# STM32_Smart.net
KiCad netlist of a schematic drawn in Altium Designer
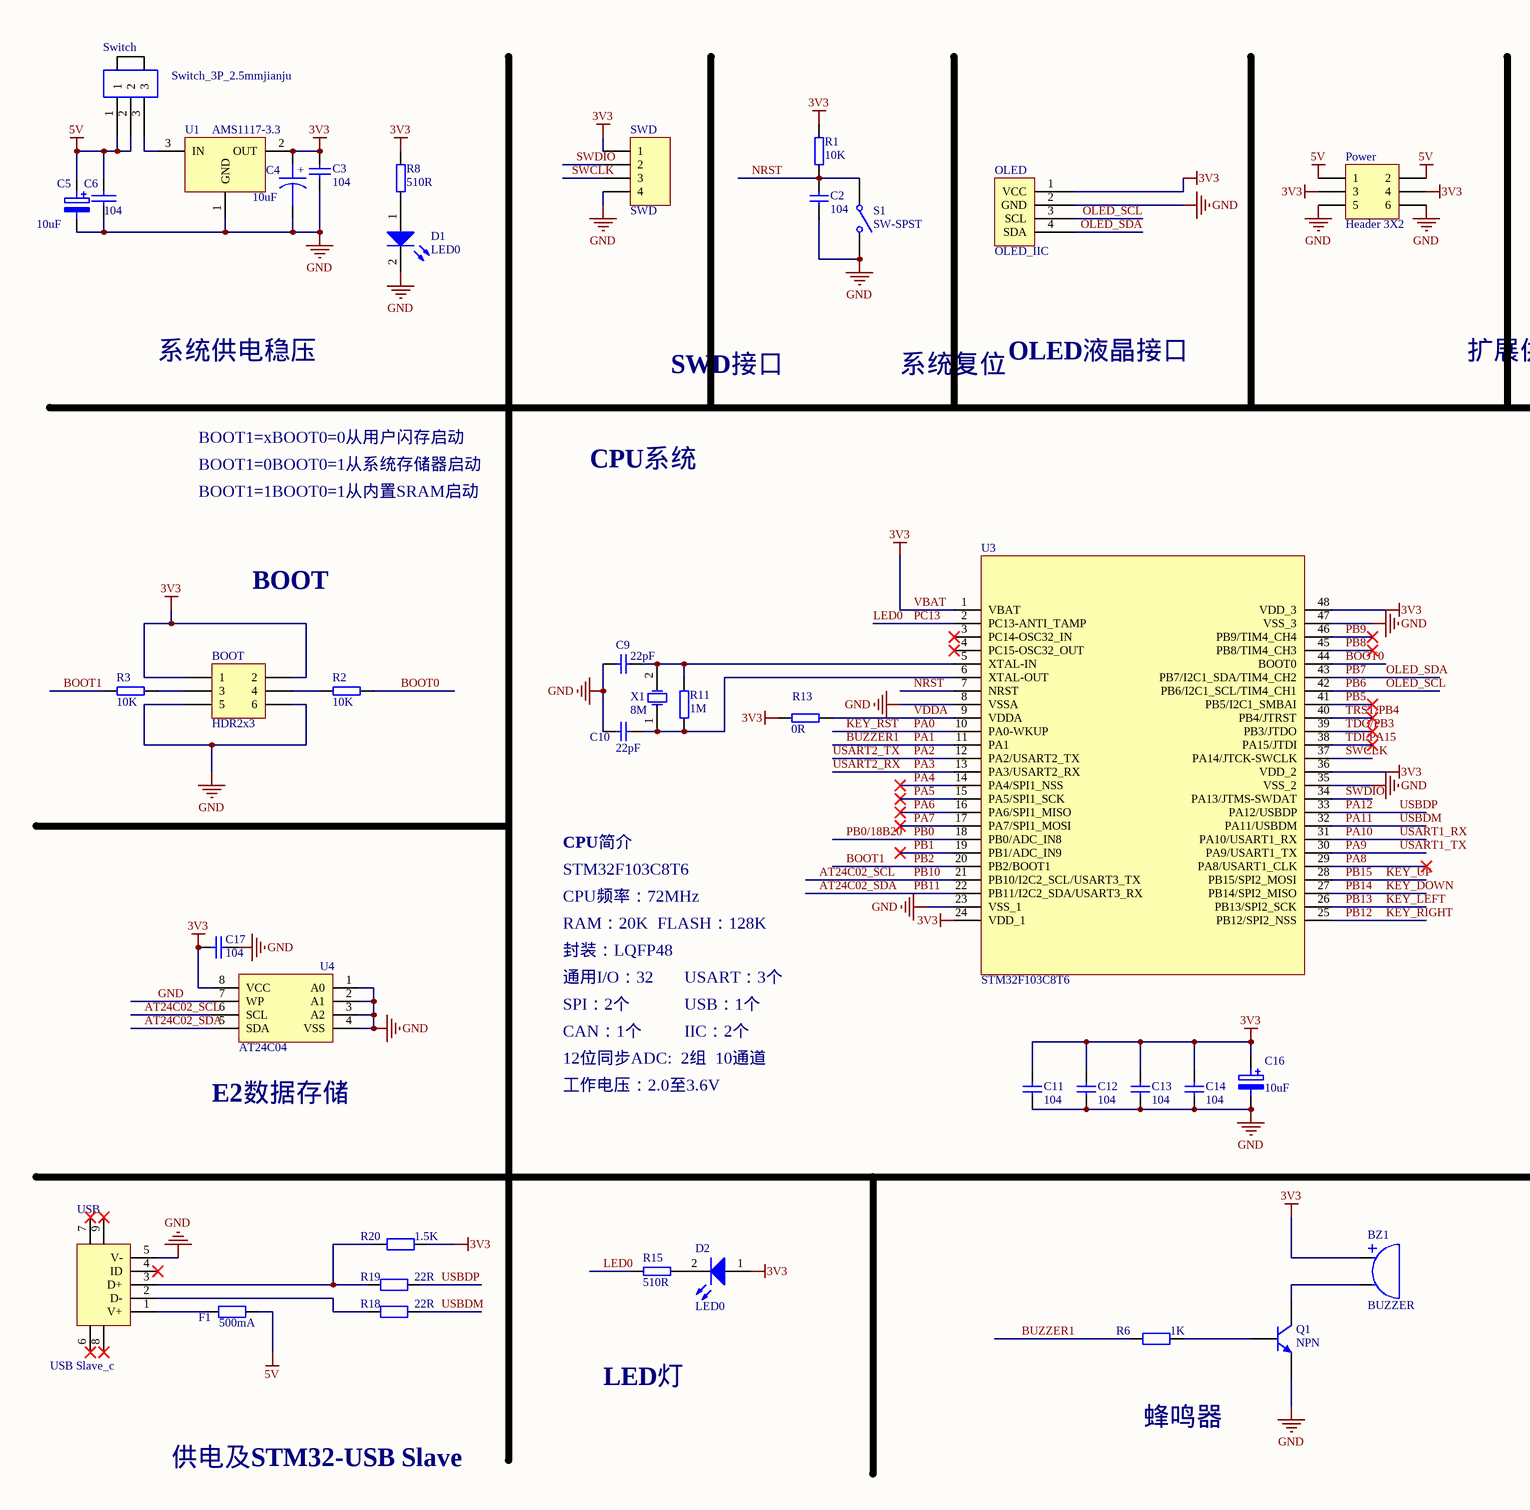
[diagram p0: STM32_Smart.SchDoc, left]
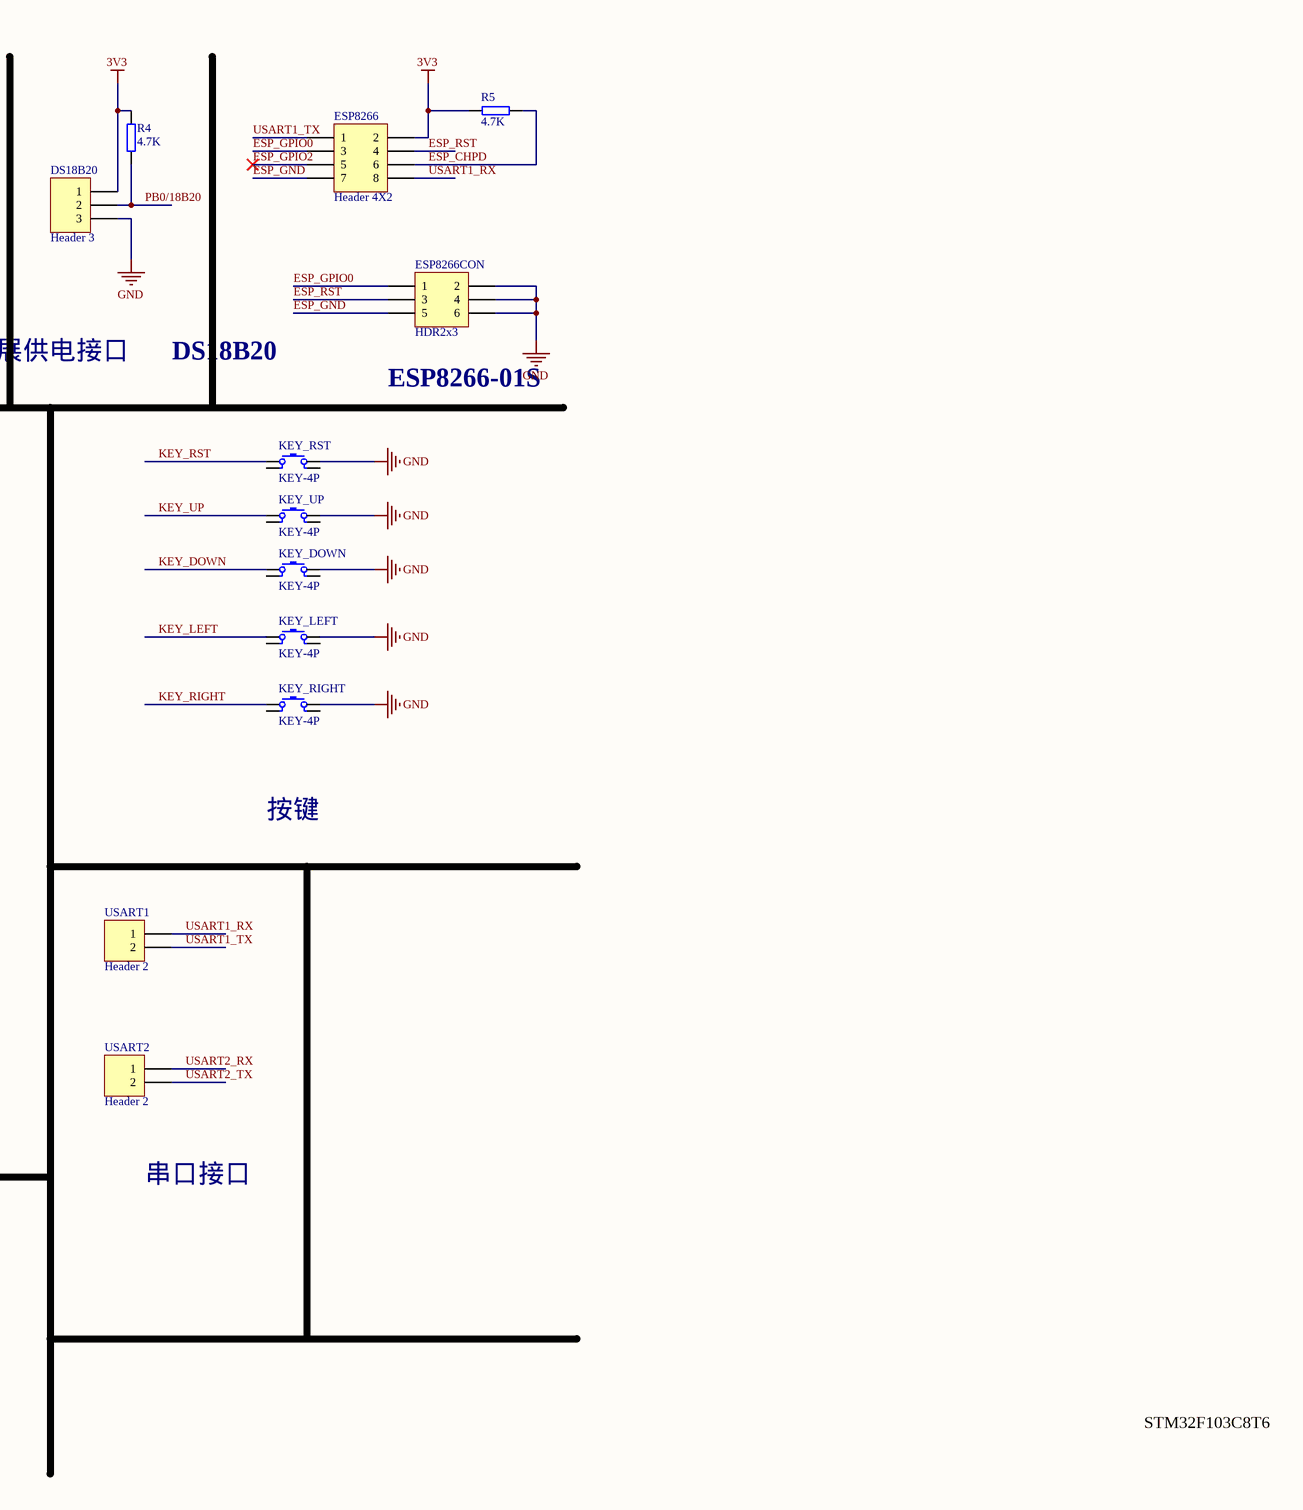
[diagram p1: STM32_Smart.SchDoc, right]

(export (version "E")
  (design (tool "Eeschema 10.0.6"))
  (components
    (comp (ref "BOOT")
      (value "HDR2x3")
      (footprint "PIN-2x3-2.54-1.0")
      (description "Connector")
      (libsource (lib "General") (part "HDR2x3"))
    )
    (comp (ref "BZ1")
      (value "BUZZER")
      (footprint "BUZZER_12*9.5_pin_7.6mm")
      (description "Buzzer")
      (libsource (lib "General") (part "BUZZER"))
    )
    (comp (ref "C2")
      (value "104")
      (footprint "RC0603")
      (description "Capacitor")
      (fields (field (name "PUBLISHER") "ZL_A0OFFICE"))
      (libsource (lib "CommomDevices") (part "CAP1"))
    )
    (comp (ref "C3")
      (value "104")
      (footprint "RC0603")
      (description "Capacitor")
      (fields (field (name "PUBLISHER") "Altium Limited"))
      (libsource (lib "*") (part "Cap"))
    )
    (comp (ref "C4")
      (value "10uF")
      (footprint "RC0805")
      (description "Capacitor")
      (libsource (lib "*") (part "CAPACITOR POL"))
    )
    (comp (ref "C5") (value "10uF") (footprint "RC0805") (libsource (lib "*") (part "ELECTRO2")))
    (comp (ref "C6")
      (value "104")
      (footprint "RC0603")
      (description "Capacitor")
      (libsource (lib "*") (part "CAP"))
    )
    (comp (ref "C9")
      (value "22pF")
      (footprint "RC0603")
      (description "Capacitor")
      (fields (field (name "PUBLISHER") "ZL_A0OFFICE"))
      (libsource (lib "CommomDevices") (part "CAP1"))
    )
    (comp (ref "C10")
      (value "22pF")
      (footprint "RC0603")
      (description "Capacitor")
      (fields (field (name "PUBLISHER") "ZL_A0OFFICE"))
      (libsource (lib "CommomDevices") (part "CAP1"))
    )
    (comp (ref "C11")
      (value "104")
      (footprint "RC0603")
      (description "Capacitor")
      (fields (field (name "PUBLISHER") "ZL_A0OFFICE"))
      (libsource (lib "CommomDevices") (part "CAP1"))
    )
    (comp (ref "C12")
      (value "104")
      (footprint "RC0603")
      (description "Capacitor")
      (fields (field (name "PUBLISHER") "ZL_A0OFFICE"))
      (libsource (lib "CommomDevices") (part "CAP1"))
    )
    (comp (ref "C13")
      (value "104")
      (footprint "RC0603")
      (description "Capacitor")
      (fields (field (name "PUBLISHER") "ZL_A0OFFICE"))
      (libsource (lib "CommomDevices") (part "CAP1"))
    )
    (comp (ref "C14")
      (value "104")
      (footprint "RC0603")
      (description "Capacitor")
      (fields (field (name "PUBLISHER") "ZL_A0OFFICE"))
      (libsource (lib "CommomDevices") (part "CAP1"))
    )
    (comp (ref "C16") (value "10uF") (footprint "RC0805") (libsource (lib "*") (part "ELECTRO2")))
    (comp (ref "C17")
      (value "104")
      (footprint "RC0603")
      (description "Capacitor")
      (libsource (lib "Miscellaneous Devices") (part "Cap"))
    )
    (comp (ref "D1")
      (value "LED0")
      (footprint "LED0805")
      (description "Typical INFRARED GaAs LED")
      (libsource (lib "Miscellaneous Devices") (part "LED0"))
    )
    (comp (ref "D2")
      (value "LED0")
      (footprint "LED0805")
      (description "Typical INFRARED GaAs LED")
      (libsource (lib "Miscellaneous Devices") (part "LED0"))
    )
    (comp (ref "DS18B20")
      (value "Header 3")
      (footprint "HDR1X3")
      (description "Header, 3-Pin")
      (fields (field (name "PUBLISHER") "Altium Limited"))
      (libsource (lib "Miscellaneous Connectors") (part "Header 3"))
    )
    (comp (ref "ESP8266")
      (value "Header 4X2")
      (footprint "HDR2X4")
      (description "Header, 4-Pin, Dual row")
      (fields (field (name "PUBLISHER") "Altium Limited"))
      (libsource (lib "Miscellaneous Connectors") (part "Header 4X2"))
    )
    (comp (ref "ESP8266CON")
      (value "HDR2x3")
      (footprint "PIN-2x3-2.54-1.0")
      (description "Connector")
      (libsource (lib "General") (part "HDR2x3"))
    )
    (comp (ref "F1")
      (value "500mA")
      (footprint "RC0805")
      (description "Resistor")
      (libsource (lib "") (part "Res2_1"))
    )
    (comp (ref "KEY_DOWN")
      (value "KEY-4P")
      (footprint "KEY_6.5x4.5")
      (description "Key")
      (libsource (lib "General") (part "KEY-4P"))
    )
    (comp (ref "KEY_LEFT")
      (value "KEY-4P")
      (footprint "KEY_6.5x4.5")
      (description "Key")
      (libsource (lib "General") (part "KEY-4P"))
    )
    (comp (ref "KEY_RIGHT")
      (value "KEY-4P")
      (footprint "KEY_6.5x4.5")
      (description "Key")
      (libsource (lib "General") (part "KEY-4P"))
    )
    (comp (ref "KEY_RST")
      (value "KEY-4P")
      (footprint "KEY_6.5x4.5")
      (description "Key")
      (libsource (lib "General") (part "KEY-4P"))
    )
    (comp (ref "KEY_UP")
      (value "KEY-4P")
      (footprint "KEY_6.5x4.5")
      (description "Key")
      (libsource (lib "General") (part "KEY-4P"))
    )
    (comp (ref "OLED")
      (value "OLED_IIC")
      (footprint "OLED_IIC")
      (libsource (lib "altium-import") (part "root_0_OLED_IIC_"))
    )
    (comp (ref "Power")
      (value "Header 3X2")
      (footprint "IDE3X2-2.54")
      (description "Header, 3-Pin, Dual row")
      (fields (field (name "PUBLISHER") "Altium Limited"))
      (libsource (lib "Miscellaneous Connectors") (part "Header 3X2"))
    )
    (comp (ref "Q1")
      (value "NPN")
      (footprint "TO-92")
      (description "NPN Bipolar Transistor")
      (fields (field (name "PUBLISHER") "Altium Limited"))
      (libsource (lib "Miscellaneous Devices") (part "NPN"))
    )
    (comp (ref "R1") (value "10K") (footprint "RC0603") (libsource (lib "ZIBO V2.0_Main") (part "R")))
    (comp (ref "R2") (value "10K") (footprint "RC0603") (libsource (lib "ZIBO V2.0_Main") (part "R")))
    (comp (ref "R3") (value "10K") (footprint "RC0603") (libsource (lib "ZIBO V2.0_Main") (part "R")))
    (comp (ref "R4") (value "4.7K") (footprint "RC0603") (libsource (lib "ZIBO V2.0_Main") (part "R")))
    (comp (ref "R5") (value "4.7K") (footprint "RC0603") (libsource (lib "ZIBO V2.0_Main") (part "R")))
    (comp (ref "R6")
      (value "1K")
      (footprint "RC0603")
      (description "Resistor")
      (libsource (lib "Miscellaneous Devices") (part "Res2"))
    )
    (comp (ref "R8") (value "510R") (footprint "RC0603") (libsource (lib "ZIBO V2.0_Main") (part "R")))
    (comp (ref "R11") (value "1M") (footprint "RC0603") (libsource (lib "ZIBO V2.0_Main") (part "R")))
    (comp (ref "R13") (value "0R") (footprint "RC0603") (libsource (lib "ZIBO V2.0_Main") (part "R")))
    (comp (ref "R15") (value "510R") (footprint "RC0603") (libsource (lib "ZIBO V2.0_Main") (part "R")))
    (comp (ref "R18")
      (value "22R")
      (footprint "RC0603")
      (description "Resistor")
      (libsource (lib "Miscellaneous Devices") (part "Res2"))
    )
    (comp (ref "R19")
      (value "22R")
      (footprint "RC0603")
      (description "Resistor")
      (libsource (lib "Miscellaneous Devices") (part "Res2"))
    )
    (comp (ref "R20")
      (value "1.5K")
      (footprint "RC0603")
      (description "Resistor")
      (libsource (lib "Miscellaneous Devices") (part "Res2"))
    )
    (comp (ref "S1")
      (value "SW-SPST")
      (footprint "SMT-KEY")
      (description "Single-Pole, Single-Throw Switch")
      (libsource (lib "Miscellaneous Devices") (part "SW-SPST"))
    )
    (comp (ref "SWD")
      (value "SWD")
      (footprint "HDR1X4")
      (description "Header, 4-Pin")
      (fields (field (name "PUBLISHER") "Altium Limited"))
      (libsource (lib "Miscellaneous Connectors") (part "Header 4"))
    )
    (comp (ref "Switch")
      (value "Switch_3P_2.5mmjianju")
      (footprint "Switch_3p_2.5mmjianju")
      (libsource (lib "STM32_Smart") (part "Switch_3P_2.5mmjianju"))
    )
    (comp (ref "U1")
      (value "AMS1117-3.3")
      (footprint "SOT223")
      (libsource (lib "Newcapec9263_Board_NEW") (part "LT1085CM-3.3"))
    )
    (comp (ref "U3")
      (value "STM32F103C8T6")
      (footprint "LQFP48")
      (libsource (lib "STM32_Smart") (part "STM32F103C8T6"))
    )
    (comp (ref "U4") (value "AT24C04") (footprint "SOIC-8P") (libsource (lib "Newcapec9263") (part "EPROM")))
    (comp (ref "USART1")
      (value "Header 2")
      (footprint "HDR1X2")
      (description "Header, 2-Pin")
      (fields (field (name "PUBLISHER") "Altium Limited"))
      (libsource (lib "Miscellaneous Connectors") (part "Header 2"))
    )
    (comp (ref "USART2")
      (value "Header 2")
      (footprint "HDR1X2")
      (description "Header, 2-Pin")
      (fields (field (name "PUBLISHER") "Altium Limited"))
      (libsource (lib "Miscellaneous Connectors") (part "Header 2"))
    )
    (comp (ref "USB")
      (value "USB Slave_c")
      (footprint "MICRO USB CONNECTOR TYPEB-ST-MC-5F-01")
      (description "USB Connector")
      (libsource (lib "General") (part "MICRO USB CONNECTOR TYPEB"))
    )
    (comp (ref "X1")
      (value "8M")
      (footprint "SMD49S")
      (description "Crystal Oscillator")
      (fields (field (name "PUBLISHER") "ZL_A0OFFICE"))
      (libsource (lib "CommomDevices") (part "XTAL_SMD"))
    )
  )
  (nets
    (net (code "1") (name "/AT24C02_SCL") (class "Default")
      (node (ref "U3") (pin "21") (pinfunction "PB10/I2C2_SCL/USART3_TX_21") (pintype "passive"))
      (node (ref "U4") (pin "6") (pinfunction "SCL_6") (pintype "passive"))
    )
    (net (code "2") (name "/AT24C02_SDA") (class "Default")
      (node (ref "U3") (pin "22") (pinfunction "PB11/I2C2_SDA/USART3_RX_22") (pintype "passive"))
      (node (ref "U4") (pin "5") (pinfunction "SDA_5") (pintype "passive"))
    )
    (net (code "3") (name "/BOOT0") (class "Default")
      (node (ref "R2") (pin "1") (pinfunction "1_1") (pintype "passive"))
      (node (ref "U3") (pin "44") (pinfunction "BOOT0_44") (pintype "passive"))
    )
    (net (code "4") (name "/BOOT1") (class "Default")
      (node (ref "R3") (pin "2") (pinfunction "2_2") (pintype "passive"))
      (node (ref "U3") (pin "20") (pinfunction "PB2/BOOT1_20") (pintype "passive"))
    )
    (net (code "5") (name "/BUZZER1") (class "Default")
      (node (ref "R6") (pin "2") (pinfunction "2_2") (pintype "passive"))
      (node (ref "U3") (pin "11") (pinfunction "PA1_11") (pintype "passive"))
    )
    (net (code "6") (name "/ESP_CHPD") (class "Default")
      (node (ref "ESP8266") (pin "6") (pinfunction "6_6") (pintype "passive"))
      (node (ref "R5") (pin "2") (pinfunction "2_2") (pintype "passive"))
    )
    (net (code "7") (name "/ESP_GND") (class "Default")
      (node (ref "ESP8266") (pin "7") (pinfunction "7_7") (pintype "passive"))
      (node (ref "ESP8266CON") (pin "5") (pinfunction "5_5") (pintype "passive"))
    )
    (net (code "8") (name "/ESP_GPIO0") (class "Default")
      (node (ref "ESP8266") (pin "3") (pinfunction "3_3") (pintype "passive"))
      (node (ref "ESP8266CON") (pin "1") (pinfunction "1_1") (pintype "passive"))
    )
    (net (code "9") (name "/ESP_GPIO2") (class "Default")
      (node (ref "ESP8266") (pin "5") (pinfunction "5_5") (pintype "passive+no_connect"))
    )
    (net (code "10") (name "/ESP_RST") (class "Default")
      (node (ref "ESP8266") (pin "4") (pinfunction "4_4") (pintype "passive"))
      (node (ref "ESP8266CON") (pin "3") (pinfunction "3_3") (pintype "passive"))
    )
    (net (code "11") (name "/KEY_DOWN") (class "Default")
      (node (ref "KEY_DOWN") (pin "1") (pinfunction "1_1") (pintype "passive"))
      (node (ref "U3") (pin "27") (pinfunction "PB14/SPI2_MISO_27") (pintype "passive"))
    )
    (net (code "12") (name "/KEY_LEFT") (class "Default")
      (node (ref "KEY_LEFT") (pin "1") (pinfunction "1_1") (pintype "passive"))
      (node (ref "U3") (pin "26") (pinfunction "PB13/SPI2_SCK_26") (pintype "passive"))
    )
    (net (code "13") (name "/KEY_RIGHT") (class "Default")
      (node (ref "KEY_RIGHT") (pin "1") (pinfunction "1_1") (pintype "passive"))
      (node (ref "U3") (pin "25") (pinfunction "PB12/SPI2_NSS_25") (pintype "passive"))
    )
    (net (code "14") (name "/KEY_RST") (class "Default")
      (node (ref "KEY_RST") (pin "1") (pinfunction "1_1") (pintype "passive"))
      (node (ref "U3") (pin "10") (pinfunction "PA0-WKUP_10") (pintype "passive"))
    )
    (net (code "15") (name "/KEY_UP") (class "Default")
      (node (ref "KEY_UP") (pin "1") (pinfunction "1_1") (pintype "passive"))
      (node (ref "U3") (pin "28") (pinfunction "PB15/SPI2_MOSI_28") (pintype "passive"))
    )
    (net (code "16") (name "/LED0") (class "Default")
      (node (ref "R15") (pin "1") (pinfunction "1_1") (pintype "passive"))
      (node (ref "U3") (pin "2") (pinfunction "PC13-ANTI_TAMP_2") (pintype "passive"))
    )
    (net (code "17") (name "/NRST") (class "Default")
      (node (ref "C2") (pin "1") (pinfunction "1_1") (pintype "passive"))
      (node (ref "R1") (pin "1") (pinfunction "1_1") (pintype "passive"))
      (node (ref "S1") (pin "1") (pinfunction "COMMON_1") (pintype "passive"))
      (node (ref "U3") (pin "7") (pinfunction "NRST_7") (pintype "passive"))
    )
    (net (code "18") (name "/OLED_SCL") (class "Default")
      (node (ref "OLED") (pin "3") (pinfunction "SCL_3") (pintype "passive"))
      (node (ref "U3") (pin "42") (pinfunction "PB6/I2C1_SCL/TIM4_CH1_42") (pintype "passive"))
    )
    (net (code "19") (name "/OLED_SDA") (class "Default")
      (node (ref "OLED") (pin "4") (pinfunction "SDA_4") (pintype "passive"))
      (node (ref "U3") (pin "43") (pinfunction "PB7/I2C1_SDA/TIM4_CH2_43") (pintype "passive"))
    )
    (net (code "20") (name "/PA2") (class "Default")
      (node (ref "U3") (pin "12") (pinfunction "PA2/USART2_TX_12") (pintype "passive"))
      (node (ref "USART2") (pin "2") (pinfunction "2_2") (pintype "passive"))
    )
    (net (code "21") (name "/PA3") (class "Default")
      (node (ref "U3") (pin "13") (pinfunction "PA3/USART2_RX_13") (pintype "passive"))
      (node (ref "USART2") (pin "1") (pinfunction "1_1") (pintype "passive"))
    )
    (net (code "22") (name "/PA4") (class "Default")
      (node (ref "U3") (pin "14") (pinfunction "PA4/SPI1_NSS_14") (pintype "passive+no_connect"))
    )
    (net (code "23") (name "/PA5") (class "Default")
      (node (ref "U3") (pin "15") (pinfunction "PA5/SPI1_SCK_15") (pintype "passive+no_connect"))
    )
    (net (code "24") (name "/PA6") (class "Default")
      (node (ref "U3") (pin "16") (pinfunction "PA6/SPI1_MISO_16") (pintype "passive+no_connect"))
    )
    (net (code "25") (name "/PA7") (class "Default")
      (node (ref "U3") (pin "17") (pinfunction "PA7/SPI1_MOSI_17") (pintype "passive+no_connect"))
    )
    (net (code "26") (name "/PA8") (class "Default")
      (node (ref "U3") (pin "29") (pinfunction "PA8/USART1_CLK_29") (pintype "passive+no_connect"))
    )
    (net (code "27") (name "/PA9") (class "Default")
      (node (ref "ESP8266") (pin "1") (pinfunction "1_1") (pintype "passive"))
      (node (ref "U3") (pin "30") (pinfunction "PA9/USART1_TX_30") (pintype "passive"))
      (node (ref "USART1") (pin "2") (pinfunction "2_2") (pintype "passive"))
    )
    (net (code "28") (name "/PA10") (class "Default")
      (node (ref "ESP8266") (pin "8") (pinfunction "8_8") (pintype "passive"))
      (node (ref "U3") (pin "31") (pinfunction "PA10/USART1_RX_31") (pintype "passive"))
      (node (ref "USART1") (pin "1") (pinfunction "1_1") (pintype "passive"))
    )
    (net (code "29") (name "/PA11") (class "Default")
      (node (ref "R18") (pin "1") (pinfunction "1_1") (pintype "passive"))
      (node (ref "U3") (pin "32") (pinfunction "PA11/USBDM_32") (pintype "passive"))
    )
    (net (code "30") (name "/PA12") (class "Default")
      (node (ref "R19") (pin "1") (pinfunction "1_1") (pintype "passive"))
      (node (ref "U3") (pin "33") (pinfunction "PA12/USBDP_33") (pintype "passive"))
    )
    (net (code "31") (name "/PB0") (class "Default")
      (node (ref "DS18B20") (pin "2") (pinfunction "2_2") (pintype "passive"))
      (node (ref "R4") (pin "2") (pinfunction "2_2") (pintype "passive"))
      (node (ref "U3") (pin "18") (pinfunction "PB0/ADC_IN8_18") (pintype "passive"))
    )
    (net (code "32") (name "/PB1") (class "Default")
      (node (ref "U3") (pin "19") (pinfunction "PB1/ADC_IN9_19") (pintype "passive+no_connect"))
    )
    (net (code "33") (name "/PB5") (class "Default")
      (node (ref "U3") (pin "41") (pinfunction "PB5/I2C1_SMBAI_41") (pintype "passive+no_connect"))
    )
    (net (code "34") (name "/PB8") (class "Default")
      (node (ref "U3") (pin "45") (pinfunction "PB8/TIM4_CH3_45") (pintype "passive+no_connect"))
    )
    (net (code "35") (name "/PB9") (class "Default")
      (node (ref "U3") (pin "46") (pinfunction "PB9/TIM4_CH4_46") (pintype "passive+no_connect"))
    )
    (net (code "36") (name "/SWCLK") (class "Default")
      (node (ref "SWD") (pin "3") (pinfunction "3_3") (pintype "passive"))
      (node (ref "U3") (pin "37") (pinfunction "PA14/JTCK-SWCLK_37") (pintype "passive"))
    )
    (net (code "37") (name "/SWDIO") (class "Default")
      (node (ref "SWD") (pin "2") (pinfunction "2_2") (pintype "passive"))
      (node (ref "U3") (pin "34") (pinfunction "PA13/JTMS-SWDAT_34") (pintype "passive"))
    )
    (net (code "38") (name "/TDI{slash}PA15") (class "Default")
      (node (ref "U3") (pin "38") (pinfunction "PA15/JTDI_38") (pintype "passive+no_connect"))
    )
    (net (code "39") (name "/TDO{slash}PB3") (class "Default")
      (node (ref "U3") (pin "39") (pinfunction "PB3/JTDO_39") (pintype "passive+no_connect"))
    )
    (net (code "40") (name "/TRST{slash}PB4") (class "Default")
      (node (ref "U3") (pin "40") (pinfunction "PB4/JTRST_40") (pintype "passive+no_connect"))
    )
    (net (code "41") (name "/VDDA") (class "Default")
      (node (ref "R13") (pin "1") (pinfunction "1_1") (pintype "passive"))
      (node (ref "U3") (pin "9") (pinfunction "VDDA_9") (pintype "passive"))
    )
    (net (code "42") (name "3V3") (class "Default")
      (node (ref "BOOT") (pin "1") (pinfunction "1_1") (pintype "passive"))
      (node (ref "BOOT") (pin "2") (pinfunction "2_2") (pintype "passive"))
      (node (ref "BZ1") (pin "1") (pinfunction "1_1") (pintype "passive"))
      (node (ref "C11") (pin "1") (pinfunction "1_1") (pintype "passive"))
      (node (ref "C12") (pin "1") (pinfunction "1_1") (pintype "passive"))
      (node (ref "C13") (pin "1") (pinfunction "1_1") (pintype "passive"))
      (node (ref "C14") (pin "1") (pinfunction "1_1") (pintype "passive"))
      (node (ref "C16") (pin "1") (pintype "passive"))
      (node (ref "C17") (pin "2") (pinfunction "2_2") (pintype "passive"))
      (node (ref "C3") (pin "1") (pinfunction "1_1") (pintype "passive"))
      (node (ref "C4") (pin "1") (pinfunction "1_1") (pintype "passive"))
      (node (ref "D2") (pin "1") (pinfunction "A_1") (pintype "passive"))
      (node (ref "DS18B20") (pin "1") (pinfunction "1_1") (pintype "passive"))
      (node (ref "ESP8266") (pin "2") (pinfunction "2_2") (pintype "passive"))
      (node (ref "OLED") (pin "1") (pinfunction "VCC_1") (pintype "passive"))
      (node (ref "Power") (pin "3") (pinfunction "3_3") (pintype "passive"))
      (node (ref "Power") (pin "4") (pinfunction "4_4") (pintype "passive"))
      (node (ref "R1") (pin "2") (pinfunction "2_2") (pintype "passive"))
      (node (ref "R13") (pin "2") (pinfunction "2_2") (pintype "passive"))
      (node (ref "R20") (pin "1") (pinfunction "1_1") (pintype "passive"))
      (node (ref "R4") (pin "1") (pinfunction "1_1") (pintype "passive"))
      (node (ref "R5") (pin "1") (pinfunction "1_1") (pintype "passive"))
      (node (ref "R8") (pin "2") (pinfunction "2_2") (pintype "passive"))
      (node (ref "SWD") (pin "1") (pinfunction "1_1") (pintype "passive"))
      (node (ref "U1") (pin "2") (pinfunction "OUT_2") (pintype "passive"))
      (node (ref "U3") (pin "1") (pinfunction "VBAT_1") (pintype "passive"))
      (node (ref "U3") (pin "24") (pinfunction "VDD_1_24") (pintype "passive"))
      (node (ref "U3") (pin "36") (pinfunction "VDD_2_36") (pintype "passive"))
      (node (ref "U3") (pin "48") (pinfunction "VDD_3_48") (pintype "passive"))
      (node (ref "U4") (pin "8") (pinfunction "VCC_8") (pintype "passive"))
    )
    (net (code "43") (name "5V") (class "Default")
      (node (ref "C5") (pin "1") (pintype "passive"))
      (node (ref "C6") (pin "1") (pinfunction "1_1") (pintype "passive"))
      (node (ref "F1") (pin "1") (pinfunction "1_1") (pintype "passive"))
      (node (ref "Power") (pin "1") (pinfunction "1_1") (pintype "passive"))
      (node (ref "Power") (pin "2") (pinfunction "2_2") (pintype "passive"))
      (node (ref "Switch") (pin "1") (pinfunction "1_1") (pintype "passive"))
      (node (ref "Switch") (pin "2") (pinfunction "2_2") (pintype "passive"))
    )
    (net (code "44") (name "GND") (class "Default")
      (node (ref "BOOT") (pin "5") (pinfunction "5_5") (pintype "passive"))
      (node (ref "BOOT") (pin "6") (pinfunction "6_6") (pintype "passive"))
      (node (ref "C10") (pin "2") (pinfunction "2_2") (pintype "passive"))
      (node (ref "C11") (pin "2") (pinfunction "2_2") (pintype "passive"))
      (node (ref "C12") (pin "2") (pinfunction "2_2") (pintype "passive"))
      (node (ref "C13") (pin "2") (pinfunction "2_2") (pintype "passive"))
      (node (ref "C14") (pin "2") (pinfunction "2_2") (pintype "passive"))
      (node (ref "C16") (pin "2") (pintype "passive"))
      (node (ref "C17") (pin "1") (pinfunction "1_1") (pintype "passive"))
      (node (ref "C2") (pin "2") (pinfunction "2_2") (pintype "passive"))
      (node (ref "C3") (pin "2") (pinfunction "2_2") (pintype "passive"))
      (node (ref "C4") (pin "2") (pinfunction "2_2") (pintype "passive"))
      (node (ref "C5") (pin "2") (pintype "passive"))
      (node (ref "C6") (pin "2") (pinfunction "2_2") (pintype "passive"))
      (node (ref "C9") (pin "2") (pinfunction "2_2") (pintype "passive"))
      (node (ref "D1") (pin "2") (pinfunction "K_2") (pintype "passive"))
      (node (ref "DS18B20") (pin "3") (pinfunction "3_3") (pintype "passive"))
      (node (ref "ESP8266CON") (pin "2") (pinfunction "2_2") (pintype "passive"))
      (node (ref "ESP8266CON") (pin "4") (pinfunction "4_4") (pintype "passive"))
      (node (ref "ESP8266CON") (pin "6") (pinfunction "6_6") (pintype "passive"))
      (node (ref "KEY_DOWN") (pin "3") (pinfunction "3_3") (pintype "passive"))
      (node (ref "KEY_LEFT") (pin "3") (pinfunction "3_3") (pintype "passive"))
      (node (ref "KEY_RIGHT") (pin "3") (pinfunction "3_3") (pintype "passive"))
      (node (ref "KEY_RST") (pin "3") (pinfunction "3_3") (pintype "passive"))
      (node (ref "KEY_UP") (pin "3") (pinfunction "3_3") (pintype "passive"))
      (node (ref "OLED") (pin "2") (pinfunction "GND_2") (pintype "passive"))
      (node (ref "Power") (pin "5") (pinfunction "5_5") (pintype "passive"))
      (node (ref "Power") (pin "6") (pinfunction "6_6") (pintype "passive"))
      (node (ref "Q1") (pin "3") (pinfunction "E_3") (pintype "passive"))
      (node (ref "S1") (pin "2") (pinfunction "NO_2") (pintype "passive"))
      (node (ref "SWD") (pin "4") (pinfunction "4_4") (pintype "passive"))
      (node (ref "U1") (pin "1") (pinfunction "GND_1") (pintype "passive"))
      (node (ref "U3") (pin "23") (pinfunction "VSS_1_23") (pintype "passive"))
      (node (ref "U3") (pin "35") (pinfunction "VSS_2_35") (pintype "passive"))
      (node (ref "U3") (pin "47") (pinfunction "VSS_3_47") (pintype "passive"))
      (node (ref "U3") (pin "8") (pinfunction "VSSA_8") (pintype "passive"))
      (node (ref "U4") (pin "1") (pinfunction "A0_1") (pintype "passive"))
      (node (ref "U4") (pin "2") (pinfunction "A1_2") (pintype "passive"))
      (node (ref "U4") (pin "3") (pinfunction "A2_3") (pintype "passive"))
      (node (ref "U4") (pin "4") (pinfunction "VSS_4") (pintype "passive"))
      (node (ref "U4") (pin "7") (pinfunction "WP_7") (pintype "passive"))
      (node (ref "USB") (pin "5") (pinfunction "V-_5") (pintype "passive"))
    )
    (net (code "45") (name "Net-(BOOT-Pad3)") (class "Default")
      (node (ref "BOOT") (pin "3") (pinfunction "3_3") (pintype "passive"))
      (node (ref "R3") (pin "1") (pinfunction "1_1") (pintype "passive"))
    )
    (net (code "46") (name "Net-(BOOT-Pad4)") (class "Default")
      (node (ref "BOOT") (pin "4") (pinfunction "4_4") (pintype "passive"))
      (node (ref "R2") (pin "2") (pinfunction "2_2") (pintype "passive"))
    )
    (net (code "47") (name "Net-(D1-A)") (class "Default")
      (node (ref "D1") (pin "1") (pinfunction "A_1") (pintype "passive"))
      (node (ref "R8") (pin "1") (pinfunction "1_1") (pintype "passive"))
    )
    (net (code "48") (name "Net-(D2-K)") (class "Default")
      (node (ref "D2") (pin "2") (pinfunction "K_2") (pintype "passive"))
      (node (ref "R15") (pin "2") (pinfunction "2_2") (pintype "passive"))
    )
    (net (code "49") (name "Net-(Q1-B)") (class "Default")
      (node (ref "Q1") (pin "2") (pinfunction "B_2") (pintype "passive"))
      (node (ref "R6") (pin "1") (pinfunction "1_1") (pintype "passive"))
    )
    (net (code "50") (name "Net-(Q1-C)") (class "Default")
      (node (ref "BZ1") (pin "2") (pinfunction "2_2") (pintype "passive"))
      (node (ref "Q1") (pin "1") (pinfunction "C_1") (pintype "passive"))
    )
    (net (code "51") (name "Net-(U1-IN)") (class "Default")
      (node (ref "Switch") (pin "3") (pinfunction "3_3") (pintype "passive"))
      (node (ref "U1") (pin "3") (pinfunction "IN_3") (pintype "passive"))
    )
    (net (code "52") (name "Net-(U3-XTAL-IN)") (class "Default")
      (node (ref "C9") (pin "1") (pinfunction "1_1") (pintype "passive"))
      (node (ref "R11") (pin "2") (pinfunction "2_2") (pintype "passive"))
      (node (ref "U3") (pin "5") (pinfunction "XTAL-IN_5") (pintype "passive"))
      (node (ref "X1") (pin "2") (pinfunction "2_2") (pintype "passive"))
    )
    (net (code "53") (name "Net-(U3-XTAL-OUT)") (class "Default")
      (node (ref "C10") (pin "1") (pinfunction "1_1") (pintype "passive"))
      (node (ref "R11") (pin "1") (pinfunction "1_1") (pintype "passive"))
      (node (ref "U3") (pin "6") (pinfunction "XTAL-OUT_6") (pintype "passive"))
      (node (ref "X1") (pin "1") (pinfunction "1_1") (pintype "passive"))
    )
    (net (code "54") (name "Net-(USB-D+)") (class "Default")
      (node (ref "R19") (pin "2") (pinfunction "2_2") (pintype "passive"))
      (node (ref "R20") (pin "2") (pinfunction "2_2") (pintype "passive"))
      (node (ref "USB") (pin "3") (pinfunction "D+_3") (pintype "passive"))
    )
    (net (code "55") (name "Net-(USB-D-)") (class "Default")
      (node (ref "R18") (pin "2") (pinfunction "2_2") (pintype "passive"))
      (node (ref "USB") (pin "2") (pinfunction "D-_2") (pintype "passive"))
    )
    (net (code "56") (name "Net-(USB-V+)") (class "Default")
      (node (ref "F1") (pin "2") (pinfunction "2_2") (pintype "passive"))
      (node (ref "USB") (pin "1") (pinfunction "V+_1") (pintype "passive"))
    )
    (net (code "57") (name "unconnected-(KEY_DOWN-Pad2)") (class "Default")
      (node (ref "KEY_DOWN") (pin "2") (pinfunction "2_2") (pintype "passive"))
    )
    (net (code "58") (name "unconnected-(KEY_DOWN-Pad4)") (class "Default")
      (node (ref "KEY_DOWN") (pin "4") (pinfunction "4_4") (pintype "passive"))
    )
    (net (code "59") (name "unconnected-(KEY_LEFT-Pad2)") (class "Default")
      (node (ref "KEY_LEFT") (pin "2") (pinfunction "2_2") (pintype "passive"))
    )
    (net (code "60") (name "unconnected-(KEY_LEFT-Pad4)") (class "Default")
      (node (ref "KEY_LEFT") (pin "4") (pinfunction "4_4") (pintype "passive"))
    )
    (net (code "61") (name "unconnected-(KEY_RIGHT-Pad2)") (class "Default")
      (node (ref "KEY_RIGHT") (pin "2") (pinfunction "2_2") (pintype "passive"))
    )
    (net (code "62") (name "unconnected-(KEY_RIGHT-Pad4)") (class "Default")
      (node (ref "KEY_RIGHT") (pin "4") (pinfunction "4_4") (pintype "passive"))
    )
    (net (code "63") (name "unconnected-(KEY_RST-Pad2)") (class "Default")
      (node (ref "KEY_RST") (pin "2") (pinfunction "2_2") (pintype "passive"))
    )
    (net (code "64") (name "unconnected-(KEY_RST-Pad4)") (class "Default")
      (node (ref "KEY_RST") (pin "4") (pinfunction "4_4") (pintype "passive"))
    )
    (net (code "65") (name "unconnected-(KEY_UP-Pad2)") (class "Default")
      (node (ref "KEY_UP") (pin "2") (pinfunction "2_2") (pintype "passive"))
    )
    (net (code "66") (name "unconnected-(KEY_UP-Pad4)") (class "Default")
      (node (ref "KEY_UP") (pin "4") (pinfunction "4_4") (pintype "passive"))
    )
    (net (code "67") (name "unconnected-(U3-PC14-OSC32_IN-Pad3)") (class "Default")
      (node (ref "U3") (pin "3") (pinfunction "PC14-OSC32_IN_3") (pintype "passive+no_connect"))
    )
    (net (code "68") (name "unconnected-(U3-PC15-OSC32_OUT-Pad4)") (class "Default")
      (node (ref "U3") (pin "4") (pinfunction "PC15-OSC32_OUT_4") (pintype "passive+no_connect"))
    )
    (net (code "69") (name "unconnected-(USB-ID-Pad4)") (class "Default")
      (node (ref "USB") (pin "4") (pinfunction "ID_4") (pintype "passive+no_connect"))
    )
    (net (code "70") (name "unconnected-(USB-Pad6)") (class "Default")
      (node (ref "USB") (pin "6") (pintype "passive+no_connect"))
    )
    (net (code "71") (name "unconnected-(USB-Pad7)") (class "Default")
      (node (ref "USB") (pin "7") (pintype "passive+no_connect"))
    )
    (net (code "72") (name "unconnected-(USB-Pad8)") (class "Default")
      (node (ref "USB") (pin "8") (pintype "passive+no_connect"))
    )
    (net (code "73") (name "unconnected-(USB-Pad9)") (class "Default")
      (node (ref "USB") (pin "9") (pintype "passive+no_connect"))
    )
  )
)
